# CITestShield.net
KiCad netlist of a schematic drawn in EAGLE
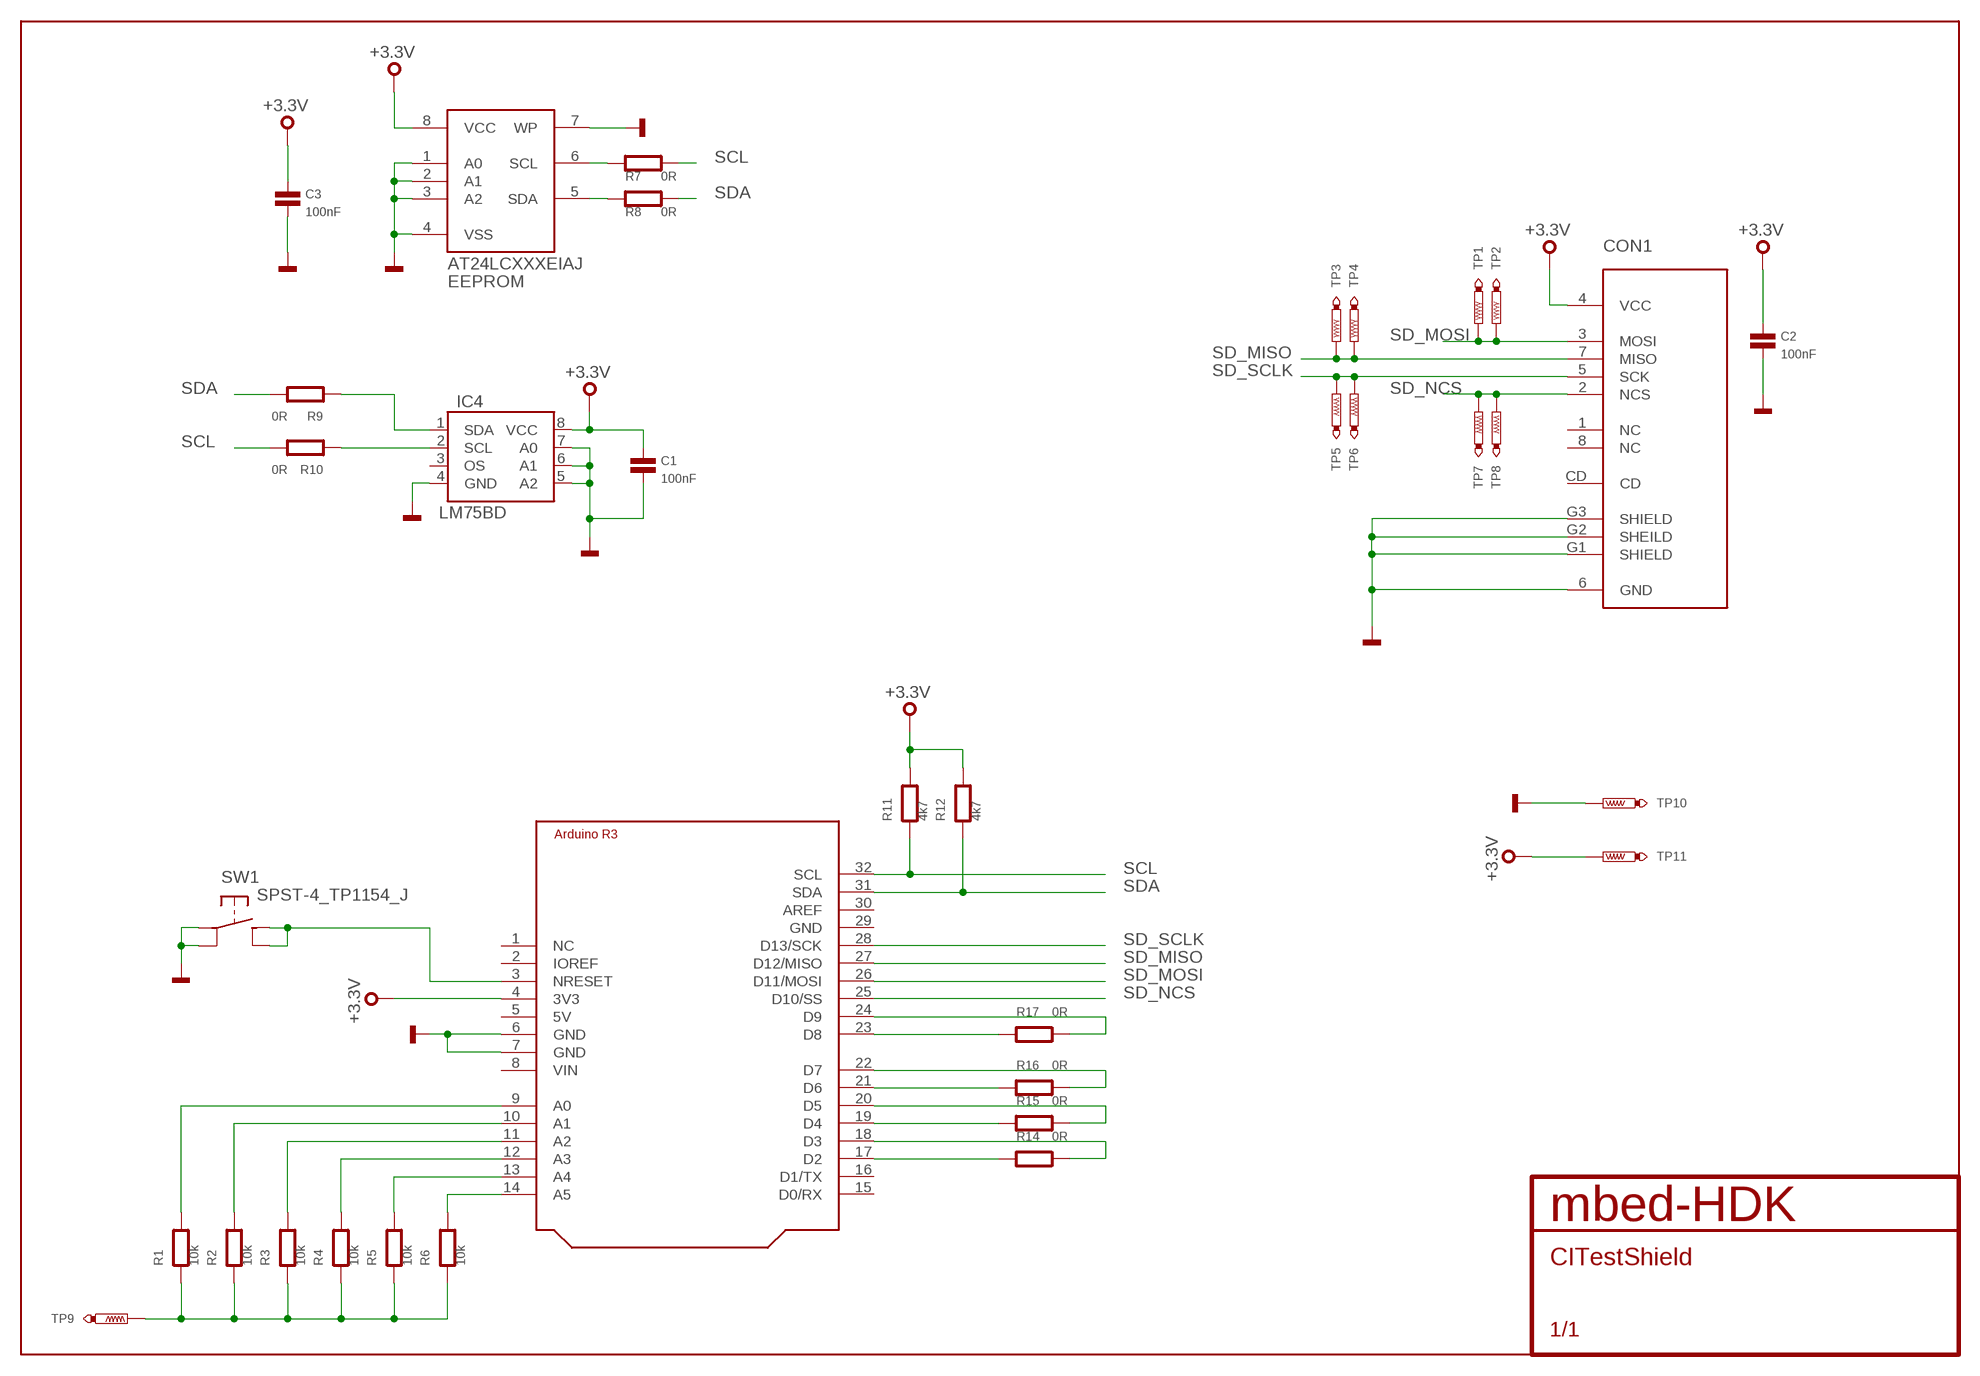
[diagram p0: schematic, sheet 1]

(export (version "E")
  (design (tool "Eeschema 10.0.6"))
  (components
    (comp (ref "BRD1")
      (value "ARDUINO-R3_SILK")
      (footprint "eagle-import:ARDUINO-R3-SILK")
      (libsource (lib "eagle-import") (part "ARDUINO-R3_SILK"))
    )
    (comp (ref "C1")
      (value "100nF")
      (footprint "eagle-import:0603")
      (libsource (lib "eagle-import") (part "C0603"))
    )
    (comp (ref "C2")
      (value "100nF")
      (footprint "eagle-import:0603")
      (libsource (lib "eagle-import") (part "C0603"))
    )
    (comp (ref "C3")
      (value "100nF")
      (footprint "eagle-import:0603")
      (libsource (lib "eagle-import") (part "C0603"))
    )
    (comp (ref "CON1")
      (value "MICRO-SD")
      (footprint "eagle-import:AMPHENOL-101-00660-68-6")
      (libsource (lib "eagle-import") (part "MICRO-SD"))
    )
    (comp (ref "EEPROM")
      (value "AT24LCXXXEIAJ")
      (footprint "eagle-import:SO08-EIAJ")
      (libsource (lib "eagle-import") (part "AT24LCXXXEIAJ"))
    )
    (comp (ref "IC4")
      (value "LM75BD")
      (footprint "eagle-import:SO8")
      (libsource (lib "eagle-import") (part "LM75BD"))
    )
    (comp (ref "R1")
      (value "10k")
      (footprint "eagle-import:0603")
      (libsource (lib "eagle-import") (part "R0603"))
    )
    (comp (ref "R2")
      (value "10k")
      (footprint "eagle-import:0603")
      (libsource (lib "eagle-import") (part "R0603"))
    )
    (comp (ref "R3")
      (value "10k")
      (footprint "eagle-import:0603")
      (libsource (lib "eagle-import") (part "R0603"))
    )
    (comp (ref "R4")
      (value "10k")
      (footprint "eagle-import:0603")
      (libsource (lib "eagle-import") (part "R0603"))
    )
    (comp (ref "R5")
      (value "10k")
      (footprint "eagle-import:0603")
      (libsource (lib "eagle-import") (part "R0603"))
    )
    (comp (ref "R6")
      (value "10k")
      (footprint "eagle-import:0603")
      (libsource (lib "eagle-import") (part "R0603"))
    )
    (comp (ref "R7")
      (value "0R")
      (footprint "eagle-import:0603")
      (libsource (lib "eagle-import") (part "R0603"))
    )
    (comp (ref "R8")
      (value "0R")
      (footprint "eagle-import:0603")
      (libsource (lib "eagle-import") (part "R0603"))
    )
    (comp (ref "R9")
      (value "0R")
      (footprint "eagle-import:0603")
      (libsource (lib "eagle-import") (part "R0603"))
    )
    (comp (ref "R10")
      (value "0R")
      (footprint "eagle-import:0603")
      (libsource (lib "eagle-import") (part "R0603"))
    )
    (comp (ref "R11")
      (value "4k7")
      (footprint "eagle-import:0603")
      (libsource (lib "eagle-import") (part "R0603"))
    )
    (comp (ref "R12")
      (value "4k7")
      (footprint "eagle-import:0603")
      (libsource (lib "eagle-import") (part "R0603"))
    )
    (comp (ref "R14")
      (value "0R")
      (footprint "eagle-import:0603")
      (libsource (lib "eagle-import") (part "R0603"))
    )
    (comp (ref "R15")
      (value "0R")
      (footprint "eagle-import:0603")
      (libsource (lib "eagle-import") (part "R0603"))
    )
    (comp (ref "R16")
      (value "0R")
      (footprint "eagle-import:0603")
      (libsource (lib "eagle-import") (part "R0603"))
    )
    (comp (ref "R17")
      (value "0R")
      (footprint "eagle-import:0603")
      (libsource (lib "eagle-import") (part "R0603"))
    )
    (comp (ref "SW1")
      (value "SPST-4_TP1154_J")
      (footprint "eagle-import:TP-1154X")
      (libsource (lib "eagle-import") (part "SPST-4_TP1154_J"))
    )
    (comp (ref "TP1")
      (value "TEST-POINT-50R-SMD")
      (footprint "eagle-import:TP50-SMD")
      (libsource (lib "eagle-import") (part "TEST-POINT-50R-SMD"))
    )
    (comp (ref "TP2")
      (value "TEST-POINT-50R-SMD")
      (footprint "eagle-import:TP50-SMD")
      (libsource (lib "eagle-import") (part "TEST-POINT-50R-SMD"))
    )
    (comp (ref "TP3")
      (value "TEST-POINT-50R-SMD")
      (footprint "eagle-import:TP50-SMD")
      (libsource (lib "eagle-import") (part "TEST-POINT-50R-SMD"))
    )
    (comp (ref "TP4")
      (value "TEST-POINT-50R-SMD")
      (footprint "eagle-import:TP50-SMD")
      (libsource (lib "eagle-import") (part "TEST-POINT-50R-SMD"))
    )
    (comp (ref "TP5")
      (value "TEST-POINT-50R-SMD")
      (footprint "eagle-import:TP50-SMD")
      (libsource (lib "eagle-import") (part "TEST-POINT-50R-SMD"))
    )
    (comp (ref "TP6")
      (value "TEST-POINT-50R-SMD")
      (footprint "eagle-import:TP50-SMD")
      (libsource (lib "eagle-import") (part "TEST-POINT-50R-SMD"))
    )
    (comp (ref "TP7")
      (value "TEST-POINT-50R-SMD")
      (footprint "eagle-import:TP50-SMD")
      (libsource (lib "eagle-import") (part "TEST-POINT-50R-SMD"))
    )
    (comp (ref "TP8")
      (value "TEST-POINT-50R-SMD")
      (footprint "eagle-import:TP50-SMD")
      (libsource (lib "eagle-import") (part "TEST-POINT-50R-SMD"))
    )
    (comp (ref "TP9")
      (value "TEST-POINT-50R-SMD")
      (footprint "eagle-import:TP50-SMD")
      (libsource (lib "eagle-import") (part "TEST-POINT-50R-SMD"))
    )
    (comp (ref "TP10")
      (value "TEST-POINT-50R-SMD")
      (footprint "eagle-import:TP50-SMD")
      (libsource (lib "eagle-import") (part "TEST-POINT-50R-SMD"))
    )
    (comp (ref "TP11")
      (value "TEST-POINT-50R-SMD")
      (footprint "eagle-import:TP50-SMD")
      (libsource (lib "eagle-import") (part "TEST-POINT-50R-SMD"))
    )
  )
  (nets
    (net (code "1") (name "+3.3V") (class "Default")
      (node (ref "BRD1") (pin "4") (pinfunction "3V3_4") (pintype "bidirectional"))
      (node (ref "C1") (pin "1") (pinfunction "P$1_1") (pintype "passive"))
      (node (ref "C2") (pin "1") (pinfunction "P$1_1") (pintype "passive"))
      (node (ref "C3") (pin "1") (pinfunction "P$1_1") (pintype "passive"))
      (node (ref "CON1") (pin "4") (pinfunction "VCC_4") (pintype "bidirectional"))
      (node (ref "EEPROM") (pin "8") (pinfunction "VCC_8") (pintype "power_in"))
      (node (ref "IC4") (pin "8") (pinfunction "VCC_8") (pintype "bidirectional"))
      (node (ref "R11") (pin "2") (pinfunction "P$2_2") (pintype "passive"))
      (node (ref "R12") (pin "2") (pinfunction "P$2_2") (pintype "passive"))
      (node (ref "TP11") (pin "TP") (pinfunction "TP_TP") (pintype "input"))
    )
    (net (code "2") (name "/SCL") (class "Default")
      (node (ref "BRD1") (pin "32") (pinfunction "SCL_32") (pintype "bidirectional"))
      (node (ref "R10") (pin "2") (pinfunction "P$2_2") (pintype "passive"))
      (node (ref "R11") (pin "1") (pinfunction "P$1_1") (pintype "passive"))
      (node (ref "R7") (pin "2") (pinfunction "P$2_2") (pintype "passive"))
    )
    (net (code "3") (name "/SDA") (class "Default")
      (node (ref "BRD1") (pin "31") (pinfunction "SDA_31") (pintype "bidirectional"))
      (node (ref "R12") (pin "1") (pinfunction "P$1_1") (pintype "passive"))
      (node (ref "R8") (pin "2") (pinfunction "P$2_2") (pintype "passive"))
      (node (ref "R9") (pin "2") (pinfunction "P$2_2") (pintype "passive"))
    )
    (net (code "4") (name "/SD_MISO") (class "Default")
      (node (ref "BRD1") (pin "27") (pinfunction "D12/MISO_27") (pintype "bidirectional"))
      (node (ref "CON1") (pin "7") (pinfunction "MISO_7") (pintype "bidirectional"))
      (node (ref "TP3") (pin "TP") (pinfunction "TP_TP") (pintype "input"))
      (node (ref "TP4") (pin "TP") (pinfunction "TP_TP") (pintype "input"))
    )
    (net (code "5") (name "/SD_MOSI") (class "Default")
      (node (ref "BRD1") (pin "26") (pinfunction "D11/MOSI_26") (pintype "bidirectional"))
      (node (ref "CON1") (pin "3") (pinfunction "MOSI_3") (pintype "bidirectional"))
      (node (ref "TP1") (pin "TP") (pinfunction "TP_TP") (pintype "input"))
      (node (ref "TP2") (pin "TP") (pinfunction "TP_TP") (pintype "input"))
    )
    (net (code "6") (name "/SD_NCS") (class "Default")
      (node (ref "BRD1") (pin "25") (pinfunction "D10/SS_25") (pintype "bidirectional"))
      (node (ref "CON1") (pin "2") (pinfunction "NCS_2") (pintype "bidirectional"))
      (node (ref "TP7") (pin "TP") (pinfunction "TP_TP") (pintype "input"))
      (node (ref "TP8") (pin "TP") (pinfunction "TP_TP") (pintype "input"))
    )
    (net (code "7") (name "/SD_SCLK") (class "Default")
      (node (ref "BRD1") (pin "28") (pinfunction "D13/SCK_28") (pintype "bidirectional"))
      (node (ref "CON1") (pin "5") (pinfunction "SCK_5") (pintype "bidirectional"))
      (node (ref "TP5") (pin "TP") (pinfunction "TP_TP") (pintype "input"))
      (node (ref "TP6") (pin "TP") (pinfunction "TP_TP") (pintype "input"))
    )
    (net (code "8") (name "GND") (class "Default")
      (node (ref "BRD1") (pin "6") (pinfunction "GND_6") (pintype "bidirectional"))
      (node (ref "BRD1") (pin "7") (pinfunction "GND_7") (pintype "bidirectional"))
      (node (ref "C1") (pin "2") (pinfunction "P$2_2") (pintype "passive"))
      (node (ref "C2") (pin "2") (pinfunction "P$2_2") (pintype "passive"))
      (node (ref "C3") (pin "2") (pinfunction "P$2_2") (pintype "passive"))
      (node (ref "CON1") (pin "6") (pinfunction "GND_6") (pintype "bidirectional"))
      (node (ref "CON1") (pin "G1") (pinfunction "SHIELD_G1") (pintype "bidirectional"))
      (node (ref "CON1") (pin "G2") (pinfunction "SHEILD_G2") (pintype "bidirectional"))
      (node (ref "CON1") (pin "G3") (pinfunction "SHIELD_G3") (pintype "bidirectional"))
      (node (ref "EEPROM") (pin "1") (pinfunction "A0_1") (pintype "bidirectional"))
      (node (ref "EEPROM") (pin "2") (pinfunction "A1_2") (pintype "bidirectional"))
      (node (ref "EEPROM") (pin "3") (pinfunction "A2_3") (pintype "bidirectional"))
      (node (ref "EEPROM") (pin "4") (pinfunction "VSS_4") (pintype "power_in"))
      (node (ref "EEPROM") (pin "7") (pinfunction "WP_7") (pintype "bidirectional"))
      (node (ref "IC4") (pin "4") (pinfunction "GND_4") (pintype "bidirectional"))
      (node (ref "IC4") (pin "5") (pinfunction "A2_5") (pintype "bidirectional"))
      (node (ref "IC4") (pin "6") (pinfunction "A1_6") (pintype "bidirectional"))
      (node (ref "IC4") (pin "7") (pinfunction "A0_7") (pintype "bidirectional"))
      (node (ref "SW1") (pin "A1") (pinfunction "A1_A1") (pintype "passive"))
      (node (ref "SW1") (pin "A2") (pinfunction "A2_A2") (pintype "passive"))
      (node (ref "TP10") (pin "TP") (pinfunction "TP_TP") (pintype "input"))
    )
    (net (code "9") (name "Net-(BRD1-A0)") (class "Default")
      (node (ref "BRD1") (pin "9") (pinfunction "A0_9") (pintype "bidirectional"))
      (node (ref "R1") (pin "2") (pinfunction "P$2_2") (pintype "passive"))
    )
    (net (code "10") (name "Net-(BRD1-A1)") (class "Default")
      (node (ref "BRD1") (pin "10") (pinfunction "A1_10") (pintype "bidirectional"))
      (node (ref "R2") (pin "2") (pinfunction "P$2_2") (pintype "passive"))
    )
    (net (code "11") (name "Net-(BRD1-A2)") (class "Default")
      (node (ref "BRD1") (pin "11") (pinfunction "A2_11") (pintype "bidirectional"))
      (node (ref "R3") (pin "2") (pinfunction "P$2_2") (pintype "passive"))
    )
    (net (code "12") (name "Net-(BRD1-A3)") (class "Default")
      (node (ref "BRD1") (pin "12") (pinfunction "A3_12") (pintype "bidirectional"))
      (node (ref "R4") (pin "2") (pinfunction "P$2_2") (pintype "passive"))
    )
    (net (code "13") (name "Net-(BRD1-A4)") (class "Default")
      (node (ref "BRD1") (pin "13") (pinfunction "A4_13") (pintype "bidirectional"))
      (node (ref "R5") (pin "2") (pinfunction "P$2_2") (pintype "passive"))
    )
    (net (code "14") (name "Net-(BRD1-A5)") (class "Default")
      (node (ref "BRD1") (pin "14") (pinfunction "A5_14") (pintype "bidirectional"))
      (node (ref "R6") (pin "2") (pinfunction "P$2_2") (pintype "passive"))
    )
    (net (code "15") (name "Net-(BRD1-D2)") (class "Default")
      (node (ref "BRD1") (pin "17") (pinfunction "D2_17") (pintype "bidirectional"))
      (node (ref "R14") (pin "1") (pinfunction "P$1_1") (pintype "passive"))
    )
    (net (code "16") (name "Net-(BRD1-D3)") (class "Default")
      (node (ref "BRD1") (pin "18") (pinfunction "D3_18") (pintype "bidirectional"))
      (node (ref "R14") (pin "2") (pinfunction "P$2_2") (pintype "passive"))
    )
    (net (code "17") (name "Net-(BRD1-D4)") (class "Default")
      (node (ref "BRD1") (pin "19") (pinfunction "D4_19") (pintype "bidirectional"))
      (node (ref "R15") (pin "1") (pinfunction "P$1_1") (pintype "passive"))
    )
    (net (code "18") (name "Net-(BRD1-D5)") (class "Default")
      (node (ref "BRD1") (pin "20") (pinfunction "D5_20") (pintype "bidirectional"))
      (node (ref "R15") (pin "2") (pinfunction "P$2_2") (pintype "passive"))
    )
    (net (code "19") (name "Net-(BRD1-D6)") (class "Default")
      (node (ref "BRD1") (pin "21") (pinfunction "D6_21") (pintype "bidirectional"))
      (node (ref "R16") (pin "1") (pinfunction "P$1_1") (pintype "passive"))
    )
    (net (code "20") (name "Net-(BRD1-D7)") (class "Default")
      (node (ref "BRD1") (pin "22") (pinfunction "D7_22") (pintype "bidirectional"))
      (node (ref "R16") (pin "2") (pinfunction "P$2_2") (pintype "passive"))
    )
    (net (code "21") (name "Net-(BRD1-D8)") (class "Default")
      (node (ref "BRD1") (pin "23") (pinfunction "D8_23") (pintype "bidirectional"))
      (node (ref "R17") (pin "1") (pinfunction "P$1_1") (pintype "passive"))
    )
    (net (code "22") (name "Net-(BRD1-D9)") (class "Default")
      (node (ref "BRD1") (pin "24") (pinfunction "D9_24") (pintype "bidirectional"))
      (node (ref "R17") (pin "2") (pinfunction "P$2_2") (pintype "passive"))
    )
    (net (code "23") (name "Net-(BRD1-NRESET)") (class "Default")
      (node (ref "BRD1") (pin "3") (pinfunction "NRESET_3") (pintype "bidirectional"))
      (node (ref "SW1") (pin "B1") (pinfunction "B1_B1") (pintype "passive"))
      (node (ref "SW1") (pin "B2") (pinfunction "B2_B2") (pintype "passive"))
    )
    (net (code "24") (name "Net-(EEPROM-SCL)") (class "Default")
      (node (ref "EEPROM") (pin "6") (pinfunction "SCL_6") (pintype "bidirectional"))
      (node (ref "R7") (pin "1") (pinfunction "P$1_1") (pintype "passive"))
    )
    (net (code "25") (name "Net-(EEPROM-SDA)") (class "Default")
      (node (ref "EEPROM") (pin "5") (pinfunction "SDA_5") (pintype "bidirectional"))
      (node (ref "R8") (pin "1") (pinfunction "P$1_1") (pintype "passive"))
    )
    (net (code "26") (name "Net-(IC4-SCL)") (class "Default")
      (node (ref "IC4") (pin "2") (pinfunction "SCL_2") (pintype "bidirectional"))
      (node (ref "R10") (pin "1") (pinfunction "P$1_1") (pintype "passive"))
    )
    (net (code "27") (name "Net-(IC4-SDA)") (class "Default")
      (node (ref "IC4") (pin "1") (pinfunction "SDA_1") (pintype "bidirectional"))
      (node (ref "R9") (pin "1") (pinfunction "P$1_1") (pintype "passive"))
    )
    (net (code "28") (name "Net-(R1-P$1)") (class "Default")
      (node (ref "R1") (pin "1") (pinfunction "P$1_1") (pintype "passive"))
      (node (ref "R2") (pin "1") (pinfunction "P$1_1") (pintype "passive"))
      (node (ref "R3") (pin "1") (pinfunction "P$1_1") (pintype "passive"))
      (node (ref "R4") (pin "1") (pinfunction "P$1_1") (pintype "passive"))
      (node (ref "R5") (pin "1") (pinfunction "P$1_1") (pintype "passive"))
      (node (ref "R6") (pin "1") (pinfunction "P$1_1") (pintype "passive"))
      (node (ref "TP9") (pin "TP") (pinfunction "TP_TP") (pintype "input"))
    )
    (net (code "29") (name "unconnected-(BRD1-5V-Pad5)") (class "Default")
      (node (ref "BRD1") (pin "5") (pinfunction "5V_5") (pintype "bidirectional"))
    )
    (net (code "30") (name "unconnected-(BRD1-AREF-Pad30)") (class "Default")
      (node (ref "BRD1") (pin "30") (pinfunction "AREF_30") (pintype "bidirectional"))
    )
    (net (code "31") (name "unconnected-(BRD1-D0{slash}RX-Pad15)") (class "Default")
      (node (ref "BRD1") (pin "15") (pinfunction "D0/RX_15") (pintype "bidirectional"))
    )
    (net (code "32") (name "unconnected-(BRD1-D1{slash}TX-Pad16)") (class "Default")
      (node (ref "BRD1") (pin "16") (pinfunction "D1/TX_16") (pintype "bidirectional"))
    )
    (net (code "33") (name "unconnected-(BRD1-GND-Pad29)") (class "Default")
      (node (ref "BRD1") (pin "29") (pinfunction "GND_29") (pintype "bidirectional"))
    )
    (net (code "34") (name "unconnected-(BRD1-IOREF-Pad2)") (class "Default")
      (node (ref "BRD1") (pin "2") (pinfunction "IOREF_2") (pintype "bidirectional"))
    )
    (net (code "35") (name "unconnected-(BRD1-NC-Pad1)") (class "Default")
      (node (ref "BRD1") (pin "1") (pinfunction "NC_1") (pintype "bidirectional"))
    )
    (net (code "36") (name "unconnected-(BRD1-VIN-Pad8)") (class "Default")
      (node (ref "BRD1") (pin "8") (pinfunction "VIN_8") (pintype "bidirectional"))
    )
    (net (code "37") (name "unconnected-(CON1-NC-Pad1)") (class "Default")
      (node (ref "CON1") (pin "1") (pinfunction "NC_1") (pintype "bidirectional"))
    )
    (net (code "38") (name "unconnected-(CON1-NC-Pad8)") (class "Default")
      (node (ref "CON1") (pin "8") (pinfunction "NC_8") (pintype "bidirectional"))
    )
    (net (code "39") (name "unconnected-(CON1-PadCD)") (class "Default")
      (node (ref "CON1") (pin "CD") (pinfunction "CD_CD") (pintype "bidirectional"))
    )
    (net (code "40") (name "unconnected-(IC4-OS-Pad3)") (class "Default")
      (node (ref "IC4") (pin "3") (pinfunction "OS_3") (pintype "bidirectional"))
    )
  )
)
